# Actuator-Scratch_-_Cole.net
KiCad netlist of a schematic drawn in EAGLE
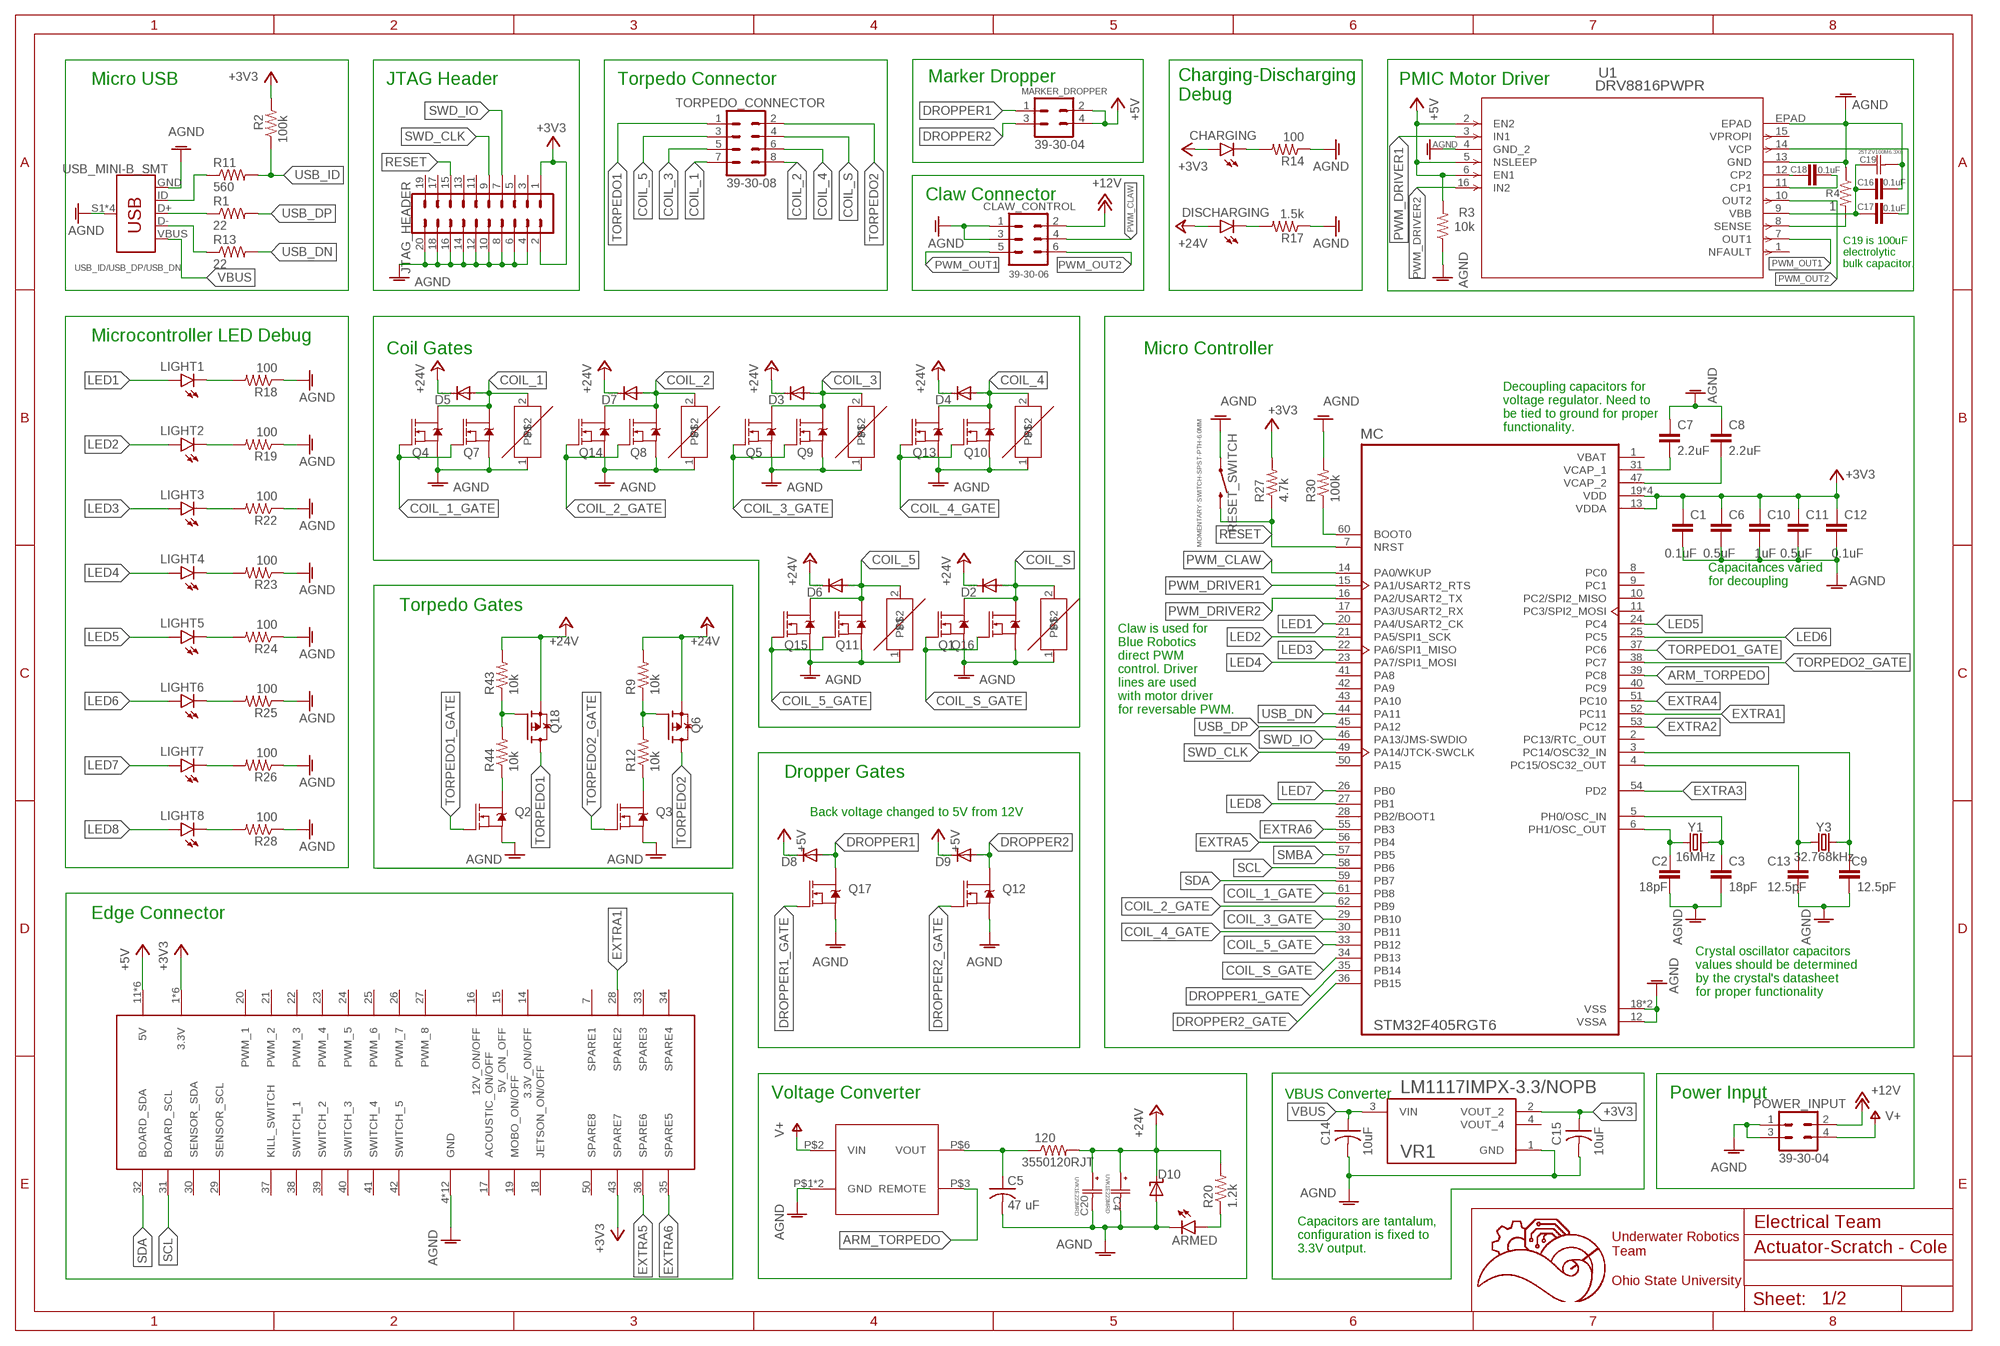
[diagram p0: schematic, sheet 1]
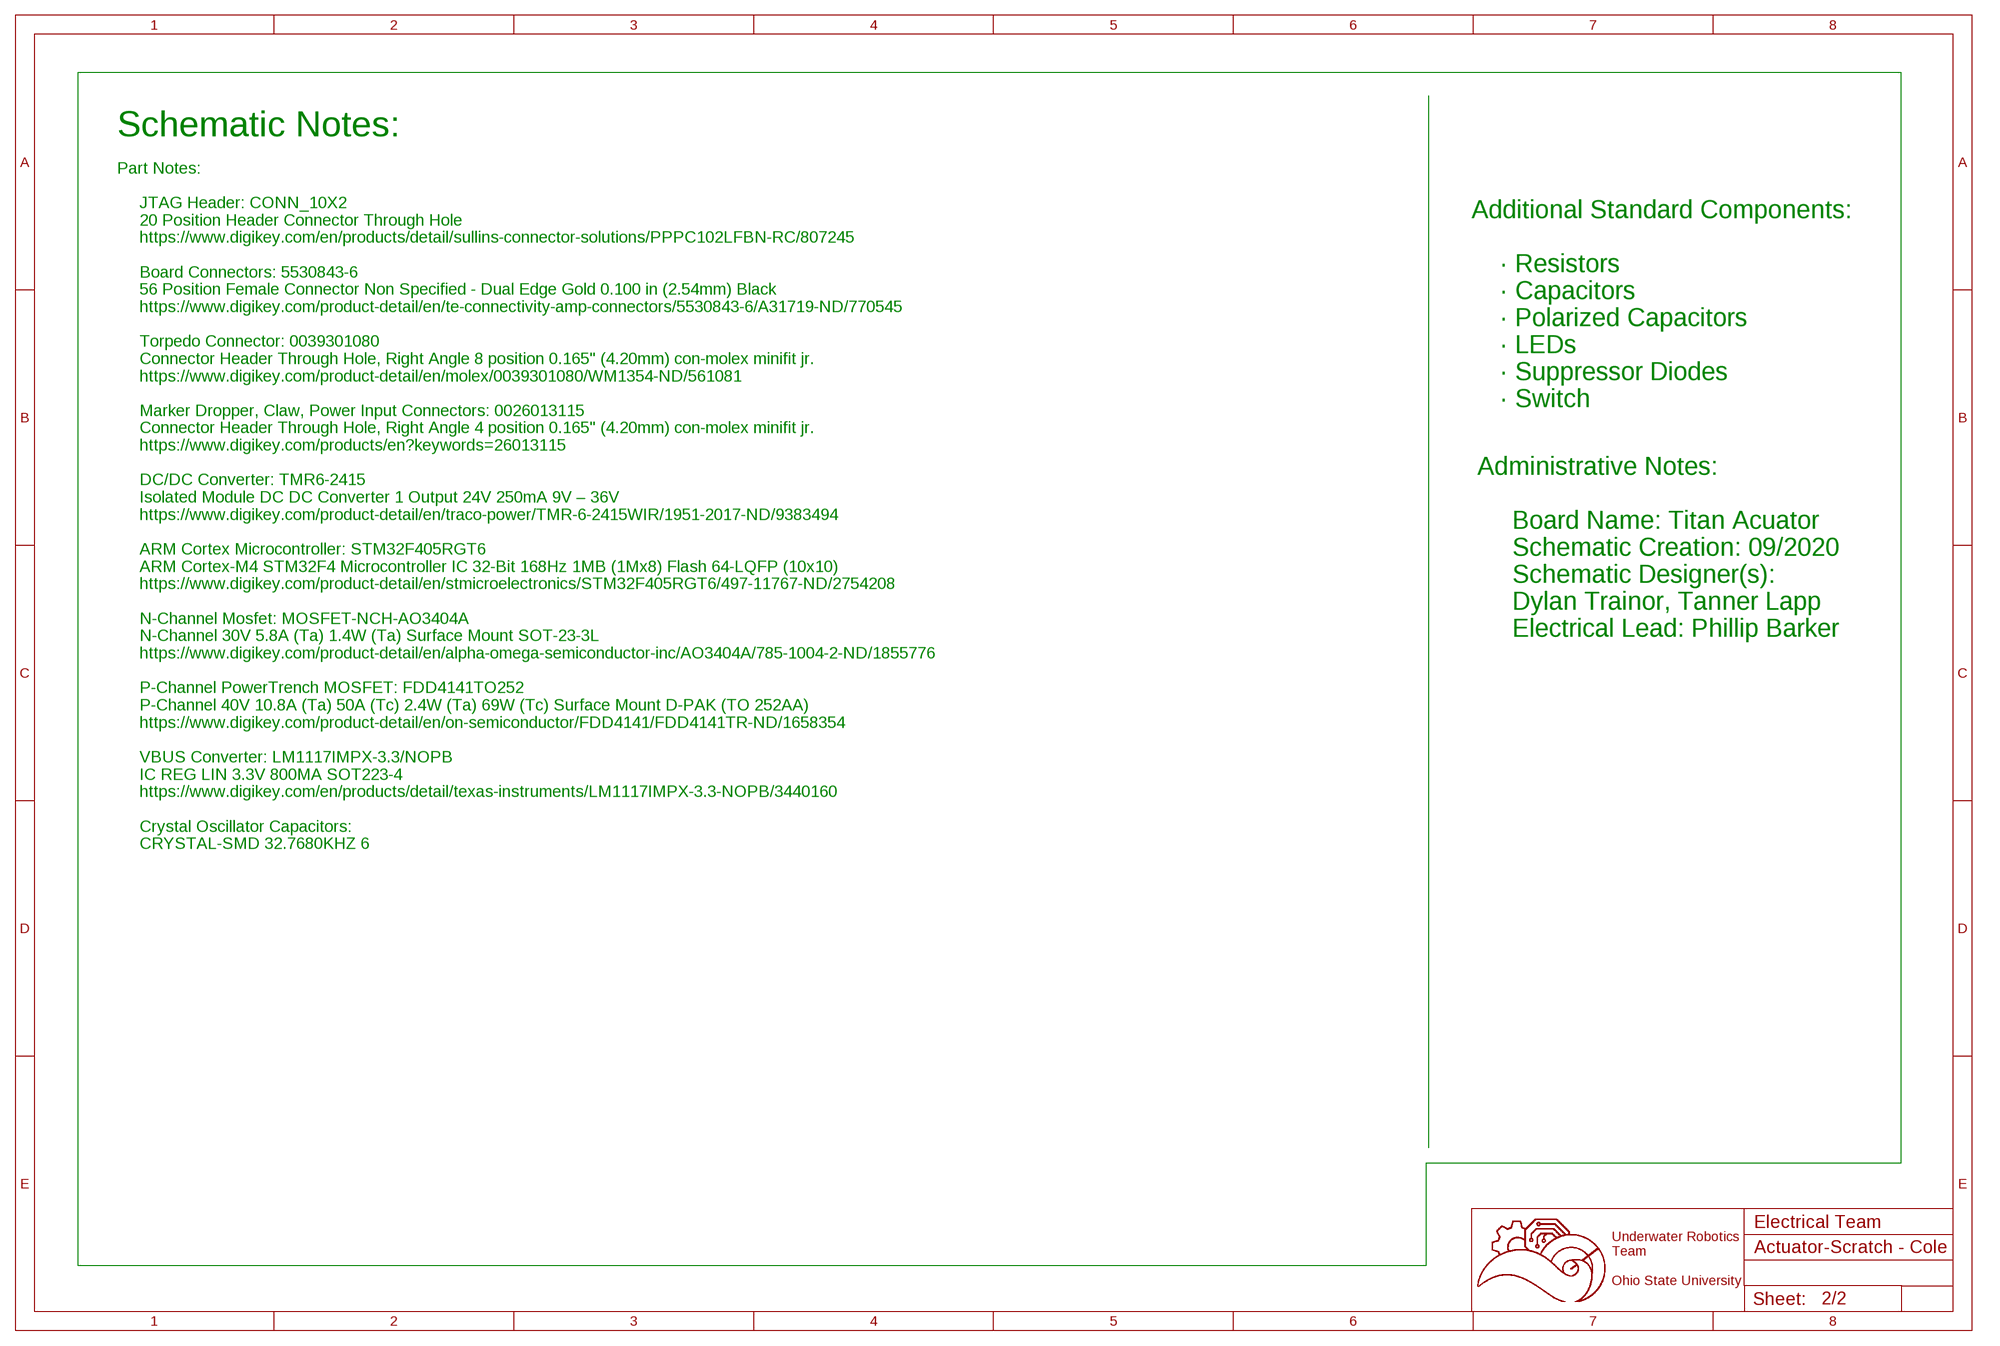
[diagram p1: schematic, sheet 2]

(export (version "E")
  (design (tool "Eeschema 10.0.6"))
  (components
    (comp (ref "120")
      (value "3550120RJT")
      (footprint "eagle-import:3550120RJT")
      (libsource (lib "eagle-import") (part "3550120RJT"))
    )
    (comp (ref "ARMED")
      (value "LEDCHIPLED_0603")
      (footprint "eagle-import:CHIPLED_0603")
      (libsource (lib "eagle-import") (part "LEDCHIPLED_0603"))
    )
    (comp (ref "C1")
      (value "0.1uF")
      (footprint "eagle-import:C0603")
      (libsource (lib "eagle-import") (part "C-EUC0603"))
    )
    (comp (ref "C2")
      (value "18pF")
      (footprint "eagle-import:C0603")
      (libsource (lib "eagle-import") (part "C-EUC0603"))
    )
    (comp (ref "C3")
      (value "18pF")
      (footprint "eagle-import:C0603")
      (libsource (lib "eagle-import") (part "C-EUC0603"))
    )
    (comp (ref "C4")
      (value "UVK1E223MRD")
      (footprint "eagle-import:CAP_UFW_25X50_NCH")
      (fields (field (name "COPYRIGHT") "Copyright (C) 2018 Accelerated Designs. All rights reserved"))
      (libsource (lib "eagle-import") (part "UVK1E223MRD"))
    )
    (comp (ref "C5")
      (value "47 uF")
      (footprint "eagle-import:C1206K")
      (libsource (lib "eagle-import") (part "resistor_348_C-USC1206K"))
    )
    (comp (ref "C6")
      (value "0.5uF")
      (footprint "eagle-import:C0603")
      (libsource (lib "eagle-import") (part "C-EUC0603"))
    )
    (comp (ref "C7")
      (value "2.2uF")
      (footprint "eagle-import:C0603")
      (libsource (lib "eagle-import") (part "C-EUC0603"))
    )
    (comp (ref "C8")
      (value "2.2uF")
      (footprint "eagle-import:C0603")
      (libsource (lib "eagle-import") (part "C-EUC0603"))
    )
    (comp (ref "C9")
      (value "12.5pF")
      (footprint "eagle-import:C0603")
      (libsource (lib "eagle-import") (part "C-EUC0603"))
    )
    (comp (ref "C10")
      (value "1uF")
      (footprint "eagle-import:C0603")
      (libsource (lib "eagle-import") (part "C-EUC0603"))
    )
    (comp (ref "C11")
      (value "0.5uF")
      (footprint "eagle-import:C0603")
      (libsource (lib "eagle-import") (part "C-EUC0603"))
    )
    (comp (ref "C12")
      (value "0.1uF")
      (footprint "eagle-import:C0603")
      (libsource (lib "eagle-import") (part "C-EUC0603"))
    )
    (comp (ref "C13")
      (value "12.5pF")
      (footprint "eagle-import:C0603")
      (libsource (lib "eagle-import") (part "C-EUC0603"))
    )
    (comp (ref "C14")
      (value "10uF")
      (footprint "eagle-import:C0603")
      (libsource (lib "eagle-import") (part "C-USC0603"))
    )
    (comp (ref "C15")
      (value "10uF")
      (footprint "eagle-import:C0603")
      (libsource (lib "eagle-import") (part "C-USC0603"))
    )
    (comp (ref "C16")
      (value "0.1uF")
      (footprint "eagle-import:C0603")
      (libsource (lib "eagle-import") (part "C-EUC0603"))
    )
    (comp (ref "C17")
      (value "0.1uF")
      (footprint "eagle-import:C0603")
      (libsource (lib "eagle-import") (part "C-EUC0603"))
    )
    (comp (ref "C18")
      (value "0.1uF")
      (footprint "eagle-import:C0603")
      (libsource (lib "eagle-import") (part "C-EUC0603"))
    )
    (comp (ref "C19")
      (value "25TZV100M6.3X8")
      (footprint "eagle-import:CAP_J-V_6P3X8_RUB")
      (fields (field (name "COPYRIGHT") "Copyright (C) 2018 Accelerated Designs. All rights reserved"))
      (libsource (lib "eagle-import") (part "25TZV100M6.3X8"))
    )
    (comp (ref "C20")
      (value "UVK1E223MRD")
      (footprint "eagle-import:CAP_UFW_25X50_NCH")
      (fields (field (name "COPYRIGHT") "Copyright (C) 2018 Accelerated Designs. All rights reserved"))
      (libsource (lib "eagle-import") (part "UVK1E223MRD"))
    )
    (comp (ref "CHARGING")
      (value "LEDCHIPLED_0603")
      (footprint "eagle-import:CHIPLED_0603")
      (libsource (lib "eagle-import") (part "LEDCHIPLED_0603"))
    )
    (comp (ref "CLAW_CONTROL")
      (value "39-30-06")
      (footprint "eagle-import:39-30-_06_")
      (libsource (lib "eagle-import") (part "39-30-?06?"))
    )
    (comp (ref "D2")
      (value "DIODE-SMB")
      (footprint "eagle-import:SMB")
      (libsource (lib "eagle-import") (part "DIODE-SMB"))
    )
    (comp (ref "D3")
      (value "DIODE-SMB")
      (footprint "eagle-import:SMB")
      (libsource (lib "eagle-import") (part "DIODE-SMB"))
    )
    (comp (ref "D4")
      (value "DIODE-SMB")
      (footprint "eagle-import:SMB")
      (libsource (lib "eagle-import") (part "DIODE-SMB"))
    )
    (comp (ref "D5")
      (value "DIODE-SMB")
      (footprint "eagle-import:SMB")
      (libsource (lib "eagle-import") (part "DIODE-SMB"))
    )
    (comp (ref "D6")
      (value "DIODE-SMB")
      (footprint "eagle-import:SMB")
      (libsource (lib "eagle-import") (part "DIODE-SMB"))
    )
    (comp (ref "D7")
      (value "DIODE-SMB")
      (footprint "eagle-import:SMB")
      (libsource (lib "eagle-import") (part "DIODE-SMB"))
    )
    (comp (ref "D8")
      (value "DIODE-SMB")
      (footprint "eagle-import:SMB")
      (libsource (lib "eagle-import") (part "DIODE-SMB"))
    )
    (comp (ref "D9")
      (value "DIODE-SMB")
      (footprint "eagle-import:SMB")
      (libsource (lib "eagle-import") (part "DIODE-SMB"))
    )
    (comp (ref "D10")
      (value "SUPPRESSOR-SMBJ")
      (footprint "eagle-import:SMBJ")
      (libsource (lib "eagle-import") (part "SUPPRESSOR-SMBJ"))
    )
    (comp (ref "DISCHARGING")
      (value "LEDCHIPLED_0603")
      (footprint "eagle-import:CHIPLED_0603")
      (libsource (lib "eagle-import") (part "LEDCHIPLED_0603"))
    )
    (comp (ref "JTAG_HEADER")
      (value "CONN_10X2")
      (footprint "eagle-import:2X10")
      (libsource (lib "eagle-import") (part "CONN_10X2"))
    )
    (comp (ref "LIGHT1")
      (value "LEDCHIPLED_0603")
      (footprint "eagle-import:CHIPLED_0603")
      (libsource (lib "eagle-import") (part "LEDCHIPLED_0603"))
    )
    (comp (ref "LIGHT2")
      (value "LEDCHIPLED_0603")
      (footprint "eagle-import:CHIPLED_0603")
      (libsource (lib "eagle-import") (part "LEDCHIPLED_0603"))
    )
    (comp (ref "LIGHT3")
      (value "LEDCHIPLED_0603")
      (footprint "eagle-import:CHIPLED_0603")
      (libsource (lib "eagle-import") (part "LEDCHIPLED_0603"))
    )
    (comp (ref "LIGHT4")
      (value "LEDCHIPLED_0603")
      (footprint "eagle-import:CHIPLED_0603")
      (libsource (lib "eagle-import") (part "LEDCHIPLED_0603"))
    )
    (comp (ref "LIGHT5")
      (value "LEDCHIPLED_0603")
      (footprint "eagle-import:CHIPLED_0603")
      (libsource (lib "eagle-import") (part "LEDCHIPLED_0603"))
    )
    (comp (ref "LIGHT6")
      (value "LEDCHIPLED_0603")
      (footprint "eagle-import:CHIPLED_0603")
      (libsource (lib "eagle-import") (part "LEDCHIPLED_0603"))
    )
    (comp (ref "LIGHT7")
      (value "LEDCHIPLED_0603")
      (footprint "eagle-import:CHIPLED_0603")
      (libsource (lib "eagle-import") (part "LEDCHIPLED_0603"))
    )
    (comp (ref "LIGHT8")
      (value "LEDCHIPLED_0603")
      (footprint "eagle-import:CHIPLED_0603")
      (libsource (lib "eagle-import") (part "LEDCHIPLED_0603"))
    )
    (comp (ref "MARKER_DROPPER")
      (value "39-30-04")
      (footprint "eagle-import:39-30-_04_")
      (libsource (lib "eagle-import") (part "39-30-?04?"))
    )
    (comp (ref "MC")
      (value "STM32F405RGT6")
      (footprint "eagle-import:QFP50P1200X1200X160-64N")
      (fields (field (name "MF") "STMicroelectronics"))
      (libsource (lib "eagle-import") (part "STM32F405RGT6"))
    )
    (comp (ref "POWER_INPUT")
      (value "39-30-04")
      (footprint "eagle-import:39-30-_04_")
      (libsource (lib "eagle-import") (part "39-30-?04?"))
    )
    (comp (ref "Q1")
      (value "MOSFET-NCH-AO3404A")
      (footprint "eagle-import:SOT23-3")
      (libsource (lib "eagle-import") (part "MOSFET-NCH-AO3404A"))
    )
    (comp (ref "Q2")
      (value "MOSFET-NCH-AO3404A")
      (footprint "eagle-import:SOT23-3")
      (libsource (lib "eagle-import") (part "MOSFET-NCH-AO3404A"))
    )
    (comp (ref "Q3")
      (value "MOSFET-NCH-AO3404A")
      (footprint "eagle-import:SOT23-3")
      (libsource (lib "eagle-import") (part "MOSFET-NCH-AO3404A"))
    )
    (comp (ref "Q4")
      (value "MOSFET-NCH-AO3404A")
      (footprint "eagle-import:SOT23-3")
      (libsource (lib "eagle-import") (part "MOSFET-NCH-AO3404A"))
    )
    (comp (ref "Q5")
      (value "MOSFET-NCH-AO3404A")
      (footprint "eagle-import:SOT23-3")
      (libsource (lib "eagle-import") (part "MOSFET-NCH-AO3404A"))
    )
    (comp (ref "Q6")
      (value "FDD4141TO252")
      (footprint "eagle-import:TO252")
      (libsource (lib "eagle-import") (part "FDD4141TO252"))
    )
    (comp (ref "Q7")
      (value "MOSFET-NCH-AO3404A")
      (footprint "eagle-import:SOT23-3")
      (libsource (lib "eagle-import") (part "MOSFET-NCH-AO3404A"))
    )
    (comp (ref "Q8")
      (value "MOSFET-NCH-AO3404A")
      (footprint "eagle-import:SOT23-3")
      (libsource (lib "eagle-import") (part "MOSFET-NCH-AO3404A"))
    )
    (comp (ref "Q9")
      (value "MOSFET-NCH-AO3404A")
      (footprint "eagle-import:SOT23-3")
      (libsource (lib "eagle-import") (part "MOSFET-NCH-AO3404A"))
    )
    (comp (ref "Q10")
      (value "MOSFET-NCH-AO3404A")
      (footprint "eagle-import:SOT23-3")
      (libsource (lib "eagle-import") (part "MOSFET-NCH-AO3404A"))
    )
    (comp (ref "Q11")
      (value "MOSFET-NCH-AO3404A")
      (footprint "eagle-import:SOT23-3")
      (libsource (lib "eagle-import") (part "MOSFET-NCH-AO3404A"))
    )
    (comp (ref "Q12")
      (value "MOSFET-NCH-AO3404A")
      (footprint "eagle-import:SOT23-3")
      (libsource (lib "eagle-import") (part "MOSFET-NCH-AO3404A"))
    )
    (comp (ref "Q13")
      (value "MOSFET-NCH-AO3404A")
      (footprint "eagle-import:SOT23-3")
      (libsource (lib "eagle-import") (part "MOSFET-NCH-AO3404A"))
    )
    (comp (ref "Q14")
      (value "MOSFET-NCH-AO3404A")
      (footprint "eagle-import:SOT23-3")
      (libsource (lib "eagle-import") (part "MOSFET-NCH-AO3404A"))
    )
    (comp (ref "Q15")
      (value "MOSFET-NCH-AO3404A")
      (footprint "eagle-import:SOT23-3")
      (libsource (lib "eagle-import") (part "MOSFET-NCH-AO3404A"))
    )
    (comp (ref "Q16")
      (value "MOSFET-NCH-AO3404A")
      (footprint "eagle-import:SOT23-3")
      (libsource (lib "eagle-import") (part "MOSFET-NCH-AO3404A"))
    )
    (comp (ref "Q17")
      (value "MOSFET-NCH-AO3404A")
      (footprint "eagle-import:SOT23-3")
      (libsource (lib "eagle-import") (part "MOSFET-NCH-AO3404A"))
    )
    (comp (ref "Q18")
      (value "FDD4141TO252")
      (footprint "eagle-import:TO252")
      (libsource (lib "eagle-import") (part "FDD4141TO252"))
    )
    (comp (ref "R1")
      (value "22")
      (footprint "eagle-import:R0603")
      (libsource (lib "eagle-import") (part "R-US_R0603"))
    )
    (comp (ref "R2")
      (value "100k")
      (footprint "eagle-import:R0603")
      (libsource (lib "eagle-import") (part "R-US_R0603"))
    )
    (comp (ref "R3")
      (value "10k")
      (footprint "eagle-import:R0603")
      (libsource (lib "eagle-import") (part "resistor_348_R-US_R0603"))
    )
    (comp (ref "R4")
      (value "1")
      (footprint "eagle-import:R0805")
      (libsource (lib "eagle-import") (part "resistor_348_R-US_R0805"))
    )
    (comp (ref "R9")
      (value "10k")
      (footprint "eagle-import:R0603")
      (libsource (lib "eagle-import") (part "resistor_348_R-US_R0603"))
    )
    (comp (ref "R11")
      (value "560")
      (footprint "eagle-import:R0603")
      (libsource (lib "eagle-import") (part "R-US_R0603"))
    )
    (comp (ref "R12")
      (value "10k")
      (footprint "eagle-import:R0603")
      (libsource (lib "eagle-import") (part "resistor_348_R-US_R0603"))
    )
    (comp (ref "R13")
      (value "22")
      (footprint "eagle-import:R0603")
      (libsource (lib "eagle-import") (part "R-US_R0603"))
    )
    (comp (ref "R14")
      (value "100")
      (footprint "eagle-import:R0805")
      (libsource (lib "eagle-import") (part "resistor_348_R-US_R0805"))
    )
    (comp (ref "R17")
      (value "1.5k")
      (footprint "eagle-import:R0805")
      (libsource (lib "eagle-import") (part "resistor_348_R-US_R0805"))
    )
    (comp (ref "R18")
      (value "100")
      (footprint "eagle-import:R0805")
      (libsource (lib "eagle-import") (part "resistor_348_R-US_R0805"))
    )
    (comp (ref "R19")
      (value "100")
      (footprint "eagle-import:R0805")
      (libsource (lib "eagle-import") (part "resistor_348_R-US_R0805"))
    )
    (comp (ref "R20")
      (value "1.2k")
      (footprint "eagle-import:R0805")
      (libsource (lib "eagle-import") (part "resistor_348_R-US_R0805"))
    )
    (comp (ref "R22")
      (value "100")
      (footprint "eagle-import:R0805")
      (libsource (lib "eagle-import") (part "resistor_348_R-US_R0805"))
    )
    (comp (ref "R23")
      (value "100")
      (footprint "eagle-import:R0805")
      (libsource (lib "eagle-import") (part "resistor_348_R-US_R0805"))
    )
    (comp (ref "R24")
      (value "100")
      (footprint "eagle-import:R0805")
      (libsource (lib "eagle-import") (part "resistor_348_R-US_R0805"))
    )
    (comp (ref "R25")
      (value "100")
      (footprint "eagle-import:R0805")
      (libsource (lib "eagle-import") (part "resistor_348_R-US_R0805"))
    )
    (comp (ref "R26")
      (value "100")
      (footprint "eagle-import:R0805")
      (libsource (lib "eagle-import") (part "resistor_348_R-US_R0805"))
    )
    (comp (ref "R27")
      (value "4.7k")
      (footprint "eagle-import:R0603")
      (libsource (lib "eagle-import") (part "R-US_R0603"))
    )
    (comp (ref "R28")
      (value "100")
      (footprint "eagle-import:R0805")
      (libsource (lib "eagle-import") (part "resistor_348_R-US_R0805"))
    )
    (comp (ref "R30")
      (value "100k")
      (footprint "eagle-import:R0603")
      (libsource (lib "eagle-import") (part "R-US_R0603"))
    )
    (comp (ref "R43")
      (value "10k")
      (footprint "eagle-import:R0603")
      (libsource (lib "eagle-import") (part "resistor_348_R-US_R0603"))
    )
    (comp (ref "R44")
      (value "10k")
      (footprint "eagle-import:R0603")
      (libsource (lib "eagle-import") (part "resistor_348_R-US_R0603"))
    )
    (comp (ref "RESET_SWITCH")
      (value "MOMENTARY-SWITCH-SPST-PTH-6.0MM")
      (footprint "eagle-import:TACTILE_SWITCH_PTH_6.0MM")
      (libsource (lib "eagle-import") (part "MOMENTARY-SWITCH-SPST-PTH-6.0MM"))
    )
    (comp (ref "TORPEDO_CONNECTOR")
      (value "39-30-08")
      (footprint "eagle-import:39-30-_08_")
      (libsource (lib "eagle-import") (part "39-30-?08?"))
    )
    (comp (ref "U$1")
      (value "5530843-EDGE")
      (footprint "eagle-import:5530843-6-BOARDFINGERS")
      (libsource (lib "eagle-import") (part "5530843-EDGE"))
    )
    (comp (ref "U$2")
      (value "ERZ-VF2M270ERZ-VF2M270")
      (footprint "eagle-import:RESM8060X320N")
      (libsource (lib "eagle-import") (part "ERZ-VF2M270ERZ-VF2M270"))
    )
    (comp (ref "U$3")
      (value "ERZ-VF2M270ERZ-VF2M270")
      (footprint "eagle-import:RESM8060X320N")
      (libsource (lib "eagle-import") (part "ERZ-VF2M270ERZ-VF2M270"))
    )
    (comp (ref "U$4")
      (value "ERZ-VF2M270ERZ-VF2M270")
      (footprint "eagle-import:RESM8060X320N")
      (libsource (lib "eagle-import") (part "ERZ-VF2M270ERZ-VF2M270"))
    )
    (comp (ref "U$5")
      (value "ERZ-VF2M270ERZ-VF2M270")
      (footprint "eagle-import:RESM8060X320N")
      (libsource (lib "eagle-import") (part "ERZ-VF2M270ERZ-VF2M270"))
    )
    (comp (ref "U$6")
      (value "TMR6-2415")
      (footprint "eagle-import:TMR6-2415")
      (libsource (lib "eagle-import") (part "TMR6-2415"))
    )
    (comp (ref "U$7")
      (value "ERZ-VF2M270ERZ-VF2M270")
      (footprint "eagle-import:RESM8060X320N")
      (libsource (lib "eagle-import") (part "ERZ-VF2M270ERZ-VF2M270"))
    )
    (comp (ref "U$8")
      (value "ERZ-VF2M270ERZ-VF2M270")
      (footprint "eagle-import:RESM8060X320N")
      (libsource (lib "eagle-import") (part "ERZ-VF2M270ERZ-VF2M270"))
    )
    (comp (ref "U1")
      (value "DRV8816PWPR")
      (footprint "eagle-import:PWP_16")
      (libsource (lib "eagle-import") (part "DRV8816PWPR"))
    )
    (comp (ref "USB_ID/USB_DP/USB_DN")
      (value "USB_MINI-B_SMT")
      (footprint "eagle-import:USB-MINIB")
      (libsource (lib "eagle-import") (part "USB_MINI-B_SMT"))
    )
    (comp (ref "VR1")
      (value "LM1117IMPX-3.3/NOPB")
      (footprint "eagle-import:VREG_LM1117IMPX-3.3_NOPB")
      (fields (field (name "MF") "Texas Instruments"))
      (libsource (lib "eagle-import") (part "LM1117IMPX-3.3/NOPB"))
    )
    (comp (ref "Y1")
      (value "16MHz")
      (footprint "eagle-import:HC49US")
      (libsource (lib "eagle-import") (part "CRYSTAL-16MHZPTH-HC49US"))
    )
    (comp (ref "Y3")
      (value "32.768kHz")
      (footprint "eagle-import:CRYSTAL-SMD-3.2X1.5MM")
      (libsource (lib "eagle-import") (part "CRYSTAL-32.768KHZSMD-3.2X1.5"))
    )
  )
  (nets
    (net (code "1") (name "+3V3") (class "Default")
      (node (ref "C1") (pin "1") (pinfunction "1_1") (pintype "passive"))
      (node (ref "C10") (pin "1") (pinfunction "1_1") (pintype "passive"))
      (node (ref "C11") (pin "1") (pinfunction "1_1") (pintype "passive"))
      (node (ref "C12") (pin "1") (pinfunction "1_1") (pintype "passive"))
      (node (ref "C15") (pin "1") (pinfunction "1_1") (pintype "passive"))
      (node (ref "C6") (pin "1") (pinfunction "1_1") (pintype "passive"))
      (node (ref "CHARGING") (pin "A") (pinfunction "A_A") (pintype "passive"))
      (node (ref "JTAG_HEADER") (pin "1") (pinfunction "1_1") (pintype "passive"))
      (node (ref "JTAG_HEADER") (pin "2") (pinfunction "2_2") (pintype "passive"))
      (node (ref "MC") (pin "13") (pinfunction "VDDA_13") (pintype "power_in"))
      (node (ref "MC") (pin "19") (pinfunction "VDD_19") (pintype "power_in"))
      (node (ref "MC") (pin "32") (pinfunction "VDD_32") (pintype "power_in"))
      (node (ref "MC") (pin "48") (pinfunction "VDD_48") (pintype "power_in"))
      (node (ref "MC") (pin "64") (pinfunction "VDD_64") (pintype "power_in"))
      (node (ref "R2") (pin "2") (pinfunction "2_2") (pintype "passive"))
      (node (ref "R27") (pin "2") (pinfunction "2_2") (pintype "passive"))
      (node (ref "U$1") (pin "1") (pinfunction "3.3V_1") (pintype "bidirectional"))
      (node (ref "U$1") (pin "2") (pinfunction "3.3V_2") (pintype "bidirectional"))
      (node (ref "U$1") (pin "3") (pinfunction "3.3V_3") (pintype "bidirectional"))
      (node (ref "U$1") (pin "43") (pinfunction "SPARE7_43") (pintype "bidirectional"))
      (node (ref "U$1") (pin "54") (pinfunction "3.3V_54") (pintype "bidirectional"))
      (node (ref "U$1") (pin "55") (pinfunction "3.3V_55") (pintype "bidirectional"))
      (node (ref "U$1") (pin "56") (pinfunction "3.3V_56") (pintype "bidirectional"))
      (node (ref "VR1") (pin "2") (pinfunction "VOUT_2_2") (pintype "output"))
    )
    (net (code "2") (name "+5V") (class "Default")
      (node (ref "D8") (pin "C") (pinfunction "C_C") (pintype "passive"))
      (node (ref "D9") (pin "C") (pinfunction "C_C") (pintype "passive"))
      (node (ref "MARKER_DROPPER") (pin "2") (pinfunction "2_2") (pintype "passive"))
      (node (ref "MARKER_DROPPER") (pin "4") (pinfunction "4_4") (pintype "passive"))
      (node (ref "R3") (pin "2") (pinfunction "2_2") (pintype "passive"))
      (node (ref "U$1") (pin "11") (pinfunction "5V_11") (pintype "bidirectional"))
      (node (ref "U$1") (pin "12") (pinfunction "5V_12") (pintype "bidirectional"))
      (node (ref "U$1") (pin "13") (pinfunction "5V_13") (pintype "bidirectional"))
      (node (ref "U$1") (pin "44") (pinfunction "5V_44") (pintype "bidirectional"))
      (node (ref "U$1") (pin "45") (pinfunction "5V_45") (pintype "bidirectional"))
      (node (ref "U$1") (pin "46") (pinfunction "5V_46") (pintype "bidirectional"))
      (node (ref "U1") (pin "2") (pinfunction "EN2_2") (pintype "input"))
      (node (ref "U1") (pin "5") (pinfunction "NSLEEP_5") (pintype "input"))
      (node (ref "U1") (pin "6") (pinfunction "EN1_6") (pintype "input"))
    )
    (net (code "3") (name "+12V") (class "Default")
      (node (ref "CLAW_CONTROL") (pin "2") (pinfunction "2_2") (pintype "passive"))
      (node (ref "POWER_INPUT") (pin "2") (pinfunction "2_2") (pintype "passive"))
    )
    (net (code "4") (name "+24V") (class "Default")
      (node (ref "120") (pin "P$2") (pinfunction "2_P$2") (pintype "passive"))
      (node (ref "C20") (pin "1") (pinfunction "1_1") (pintype "passive"))
      (node (ref "C4") (pin "1") (pinfunction "1_1") (pintype "passive"))
      (node (ref "D10") (pin "C") (pinfunction "C_C") (pintype "passive"))
      (node (ref "D2") (pin "C") (pinfunction "C_C") (pintype "passive"))
      (node (ref "D3") (pin "C") (pinfunction "C_C") (pintype "passive"))
      (node (ref "D4") (pin "C") (pinfunction "C_C") (pintype "passive"))
      (node (ref "D5") (pin "C") (pinfunction "C_C") (pintype "passive"))
      (node (ref "D6") (pin "C") (pinfunction "C_C") (pintype "passive"))
      (node (ref "D7") (pin "C") (pinfunction "C_C") (pintype "passive"))
      (node (ref "DISCHARGING") (pin "A") (pinfunction "A_A") (pintype "passive"))
      (node (ref "Q18") (pin "2") (pinfunction "S_2") (pintype "passive"))
      (node (ref "Q6") (pin "2") (pinfunction "S_2") (pintype "passive"))
      (node (ref "R20") (pin "2") (pinfunction "2_2") (pintype "passive"))
      (node (ref "R43") (pin "2") (pinfunction "2_2") (pintype "passive"))
      (node (ref "R9") (pin "2") (pinfunction "2_2") (pintype "passive"))
    )
    (net (code "5") (name "AGND") (class "Default")
      (node (ref "ARMED") (pin "C") (pinfunction "C_C") (pintype "passive"))
      (node (ref "C1") (pin "2") (pinfunction "2_2") (pintype "passive"))
      (node (ref "C10") (pin "2") (pinfunction "2_2") (pintype "passive"))
      (node (ref "C11") (pin "2") (pinfunction "2_2") (pintype "passive"))
      (node (ref "C12") (pin "2") (pinfunction "2_2") (pintype "passive"))
      (node (ref "C13") (pin "2") (pinfunction "2_2") (pintype "passive"))
      (node (ref "C14") (pin "2") (pinfunction "2_2") (pintype "passive"))
      (node (ref "C15") (pin "2") (pinfunction "2_2") (pintype "passive"))
      (node (ref "C16") (pin "2") (pinfunction "2_2") (pintype "passive"))
      (node (ref "C19") (pin "2") (pinfunction "2_2") (pintype "passive"))
      (node (ref "C2") (pin "2") (pinfunction "2_2") (pintype "passive"))
      (node (ref "C20") (pin "2") (pinfunction "2_2") (pintype "passive"))
      (node (ref "C3") (pin "2") (pinfunction "2_2") (pintype "passive"))
      (node (ref "C4") (pin "2") (pinfunction "2_2") (pintype "passive"))
      (node (ref "C5") (pin "2") (pinfunction "2_2") (pintype "passive"))
      (node (ref "C6") (pin "2") (pinfunction "2_2") (pintype "passive"))
      (node (ref "C7") (pin "1") (pinfunction "1_1") (pintype "passive"))
      (node (ref "C8") (pin "1") (pinfunction "1_1") (pintype "passive"))
      (node (ref "C9") (pin "2") (pinfunction "2_2") (pintype "passive"))
      (node (ref "CLAW_CONTROL") (pin "1") (pinfunction "1_1") (pintype "passive"))
      (node (ref "CLAW_CONTROL") (pin "3") (pinfunction "3_3") (pintype "passive"))
      (node (ref "D10") (pin "A") (pinfunction "A_A") (pintype "passive"))
      (node (ref "JTAG_HEADER") (pin "10") (pinfunction "10_10") (pintype "passive"))
      (node (ref "JTAG_HEADER") (pin "12") (pinfunction "12_12") (pintype "passive"))
      (node (ref "JTAG_HEADER") (pin "14") (pinfunction "14_14") (pintype "passive"))
      (node (ref "JTAG_HEADER") (pin "16") (pinfunction "16_16") (pintype "passive"))
      (node (ref "JTAG_HEADER") (pin "18") (pinfunction "18_18") (pintype "passive"))
      (node (ref "JTAG_HEADER") (pin "20") (pinfunction "20_20") (pintype "passive"))
      (node (ref "JTAG_HEADER") (pin "4") (pinfunction "4_4") (pintype "passive"))
      (node (ref "JTAG_HEADER") (pin "6") (pinfunction "6_6") (pintype "passive"))
      (node (ref "JTAG_HEADER") (pin "8") (pinfunction "8_8") (pintype "passive"))
      (node (ref "MC") (pin "12") (pinfunction "VSSA_12") (pintype "power_in"))
      (node (ref "MC") (pin "18") (pinfunction "VSS_18") (pintype "power_in"))
      (node (ref "MC") (pin "63") (pinfunction "VSS_63") (pintype "power_in"))
      (node (ref "POWER_INPUT") (pin "1") (pinfunction "1_1") (pintype "passive"))
      (node (ref "POWER_INPUT") (pin "3") (pinfunction "3_3") (pintype "passive"))
      (node (ref "Q1") (pin "2") (pinfunction "S_2") (pintype "bidirectional"))
      (node (ref "Q10") (pin "2") (pinfunction "S_2") (pintype "bidirectional"))
      (node (ref "Q11") (pin "2") (pinfunction "S_2") (pintype "bidirectional"))
      (node (ref "Q12") (pin "2") (pinfunction "S_2") (pintype "bidirectional"))
      (node (ref "Q13") (pin "2") (pinfunction "S_2") (pintype "bidirectional"))
      (node (ref "Q14") (pin "2") (pinfunction "S_2") (pintype "bidirectional"))
      (node (ref "Q15") (pin "2") (pinfunction "S_2") (pintype "bidirectional"))
      (node (ref "Q16") (pin "2") (pinfunction "S_2") (pintype "bidirectional"))
      (node (ref "Q17") (pin "2") (pinfunction "S_2") (pintype "bidirectional"))
      (node (ref "Q2") (pin "2") (pinfunction "S_2") (pintype "bidirectional"))
      (node (ref "Q3") (pin "2") (pinfunction "S_2") (pintype "bidirectional"))
      (node (ref "Q4") (pin "2") (pinfunction "S_2") (pintype "bidirectional"))
      (node (ref "Q5") (pin "2") (pinfunction "S_2") (pintype "bidirectional"))
      (node (ref "Q7") (pin "2") (pinfunction "S_2") (pintype "bidirectional"))
      (node (ref "Q8") (pin "2") (pinfunction "S_2") (pintype "bidirectional"))
      (node (ref "Q9") (pin "2") (pinfunction "S_2") (pintype "bidirectional"))
      (node (ref "R14") (pin "1") (pinfunction "1_1") (pintype "passive"))
      (node (ref "R17") (pin "1") (pinfunction "1_1") (pintype "passive"))
      (node (ref "R18") (pin "1") (pinfunction "1_1") (pintype "passive"))
      (node (ref "R19") (pin "1") (pinfunction "1_1") (pintype "passive"))
      (node (ref "R22") (pin "1") (pinfunction "1_1") (pintype "passive"))
      (node (ref "R23") (pin "1") (pinfunction "1_1") (pintype "passive"))
      (node (ref "R24") (pin "1") (pinfunction "1_1") (pintype "passive"))
      (node (ref "R25") (pin "1") (pinfunction "1_1") (pintype "passive"))
      (node (ref "R26") (pin "1") (pinfunction "1_1") (pintype "passive"))
      (node (ref "R28") (pin "1") (pinfunction "1_1") (pintype "passive"))
      (node (ref "R3") (pin "1") (pinfunction "1_1") (pintype "passive"))
      (node (ref "R30") (pin "2") (pinfunction "2_2") (pintype "passive"))
      (node (ref "R4") (pin "1") (pinfunction "1_1") (pintype "passive"))
      (node (ref "RESET_SWITCH") (pin "1") (pinfunction "1_1") (pintype "passive"))
      (node (ref "U$1") (pin "10") (pinfunction "GND_10") (pintype "bidirectional"))
      (node (ref "U$1") (pin "4") (pinfunction "GND_4") (pintype "bidirectional"))
      (node (ref "U$1") (pin "47") (pinfunction "GND_47") (pintype "bidirectional"))
      (node (ref "U$1") (pin "48") (pinfunction "GND_48") (pintype "bidirectional"))
      (node (ref "U$1") (pin "49") (pinfunction "GND_49") (pintype "bidirectional"))
      (node (ref "U$1") (pin "5") (pinfunction "GND_5") (pintype "bidirectional"))
      (node (ref "U$1") (pin "51") (pinfunction "GND_51") (pintype "bidirectional"))
      (node (ref "U$1") (pin "52") (pinfunction "GND_52") (pintype "bidirectional"))
      (node (ref "U$1") (pin "53") (pinfunction "GND_53") (pintype "bidirectional"))
      (node (ref "U$1") (pin "6") (pinfunction "GND_6") (pintype "bidirectional"))
      (node (ref "U$1") (pin "8") (pinfunction "GND_8") (pintype "bidirectional"))
      (node (ref "U$1") (pin "9") (pinfunction "GND_9") (pintype "bidirectional"))
      (node (ref "U$2") (pin "1") (pinfunction "P$1_1") (pintype "bidirectional"))
      (node (ref "U$3") (pin "1") (pinfunction "P$1_1") (pintype "bidirectional"))
      (node (ref "U$4") (pin "1") (pinfunction "P$1_1") (pintype "bidirectional"))
      (node (ref "U$5") (pin "1") (pinfunction "P$1_1") (pintype "bidirectional"))
      (node (ref "U$6") (pin "P$1") (pinfunction "GND_P$1") (pintype "bidirectional"))
      (node (ref "U$6") (pin "P$7") (pinfunction "GND_P$7") (pintype "bidirectional"))
      (node (ref "U$7") (pin "1") (pinfunction "P$1_1") (pintype "bidirectional"))
      (node (ref "U$8") (pin "1") (pinfunction "P$1_1") (pintype "bidirectional"))
      (node (ref "U1") (pin "13") (pinfunction "GND_13") (pintype "power_in"))
      (node (ref "U1") (pin "4") (pinfunction "GND_2_4") (pintype "power_in"))
      (node (ref "U1") (pin "EPAD") (pinfunction "EPAD_EPAD") (pintype "passive"))
      (node (ref "USB_ID/USB_DP/USB_DN") (pin "GND") (pinfunction "GND_GND") (pintype "power_in"))
      (node (ref "USB_ID/USB_DP/USB_DN") (pin "S1") (pinfunction "SHIELD_S1") (pintype "bidirectional"))
      (node (ref "USB_ID/USB_DP/USB_DN") (pin "S2") (pinfunction "SHIELD_S2") (pintype "bidirectional"))
      (node (ref "USB_ID/USB_DP/USB_DN") (pin "S3") (pinfunction "SHIELD_S3") (pintype "bidirectional"))
      (node (ref "USB_ID/USB_DP/USB_DN") (pin "S4") (pinfunction "SHIELD_S4") (pintype "bidirectional"))
      (node (ref "VR1") (pin "1") (pinfunction "GND_1") (pintype "power_in"))
    )
    (net (code "6") (name "ARM_TORPEDO") (class "Default")
      (node (ref "MC") (pin "39") (pinfunction "PC8_39") (pintype "bidirectional"))
      (node (ref "U$6") (pin "P$3") (pinfunction "REMOTE_P$3") (pintype "bidirectional"))
    )
    (net (code "7") (name "COIL_1") (class "Default")
      (node (ref "D5") (pin "A") (pinfunction "A_A") (pintype "passive"))
      (node (ref "Q4") (pin "3") (pinfunction "D_3") (pintype "bidirectional"))
      (node (ref "Q7") (pin "3") (pinfunction "D_3") (pintype "bidirectional"))
      (node (ref "TORPEDO_CONNECTOR") (pin "7") (pinfunction "7_7") (pintype "passive"))
      (node (ref "U$8") (pin "2") (pinfunction "P$2_2") (pintype "bidirectional"))
    )
    (net (code "8") (name "COIL_1_GATE") (class "Default")
      (node (ref "MC") (pin "61") (pinfunction "PB8_61") (pintype "bidirectional"))
      (node (ref "Q4") (pin "1") (pinfunction "G_1") (pintype "bidirectional"))
      (node (ref "Q7") (pin "1") (pinfunction "G_1") (pintype "bidirectional"))
    )
    (net (code "9") (name "COIL_2") (class "Default")
      (node (ref "D7") (pin "A") (pinfunction "A_A") (pintype "passive"))
      (node (ref "Q14") (pin "3") (pinfunction "D_3") (pintype "bidirectional"))
      (node (ref "Q8") (pin "3") (pinfunction "D_3") (pintype "bidirectional"))
      (node (ref "TORPEDO_CONNECTOR") (pin "8") (pinfunction "8_8") (pintype "passive"))
      (node (ref "U$7") (pin "2") (pinfunction "P$2_2") (pintype "bidirectional"))
    )
    (net (code "10") (name "COIL_2_GATE") (class "Default")
      (node (ref "MC") (pin "62") (pinfunction "PB9_62") (pintype "bidirectional"))
      (node (ref "Q14") (pin "1") (pinfunction "G_1") (pintype "bidirectional"))
      (node (ref "Q8") (pin "1") (pinfunction "G_1") (pintype "bidirectional"))
    )
    (net (code "11") (name "COIL_3") (class "Default")
      (node (ref "D3") (pin "A") (pinfunction "A_A") (pintype "passive"))
      (node (ref "Q5") (pin "3") (pinfunction "D_3") (pintype "bidirectional"))
      (node (ref "Q9") (pin "3") (pinfunction "D_3") (pintype "bidirectional"))
      (node (ref "TORPEDO_CONNECTOR") (pin "5") (pinfunction "5_5") (pintype "passive"))
      (node (ref "U$5") (pin "2") (pinfunction "P$2_2") (pintype "bidirectional"))
    )
    (net (code "12") (name "COIL_3_GATE") (class "Default")
      (node (ref "MC") (pin "29") (pinfunction "PB10_29") (pintype "bidirectional"))
      (node (ref "Q5") (pin "1") (pinfunction "G_1") (pintype "bidirectional"))
      (node (ref "Q9") (pin "1") (pinfunction "G_1") (pintype "bidirectional"))
    )
    (net (code "13") (name "COIL_4") (class "Default")
      (node (ref "D4") (pin "A") (pinfunction "A_A") (pintype "passive"))
      (node (ref "Q10") (pin "3") (pinfunction "D_3") (pintype "bidirectional"))
      (node (ref "Q13") (pin "3") (pinfunction "D_3") (pintype "bidirectional"))
      (node (ref "TORPEDO_CONNECTOR") (pin "6") (pinfunction "6_6") (pintype "passive"))
      (node (ref "U$4") (pin "2") (pinfunction "P$2_2") (pintype "bidirectional"))
    )
    (net (code "14") (name "COIL_4_GATE") (class "Default")
      (node (ref "MC") (pin "30") (pinfunction "PB11_30") (pintype "bidirectional"))
      (node (ref "Q10") (pin "1") (pinfunction "G_1") (pintype "bidirectional"))
      (node (ref "Q13") (pin "1") (pinfunction "G_1") (pintype "bidirectional"))
    )
    (net (code "15") (name "COIL_5") (class "Default")
      (node (ref "D6") (pin "A") (pinfunction "A_A") (pintype "passive"))
      (node (ref "Q11") (pin "3") (pinfunction "D_3") (pintype "bidirectional"))
      (node (ref "Q15") (pin "3") (pinfunction "D_3") (pintype "bidirectional"))
      (node (ref "TORPEDO_CONNECTOR") (pin "3") (pinfunction "3_3") (pintype "passive"))
      (node (ref "U$3") (pin "2") (pinfunction "P$2_2") (pintype "bidirectional"))
    )
    (net (code "16") (name "COIL_5_GATE") (class "Default")
      (node (ref "MC") (pin "33") (pinfunction "PB12_33") (pintype "bidirectional"))
      (node (ref "Q11") (pin "1") (pinfunction "G_1") (pintype "bidirectional"))
      (node (ref "Q15") (pin "1") (pinfunction "G_1") (pintype "bidirectional"))
    )
    (net (code "17") (name "COIL_S") (class "Default")
      (node (ref "D2") (pin "A") (pinfunction "A_A") (pintype "passive"))
      (node (ref "Q1") (pin "3") (pinfunction "D_3") (pintype "bidirectional"))
      (node (ref "Q16") (pin "3") (pinfunction "D_3") (pintype "bidirectional"))
      (node (ref "TORPEDO_CONNECTOR") (pin "4") (pinfunction "4_4") (pintype "passive"))
      (node (ref "U$2") (pin "2") (pinfunction "P$2_2") (pintype "bidirectional"))
    )
    (net (code "18") (name "COIL_S_GATE") (class "Default")
      (node (ref "MC") (pin "34") (pinfunction "PB13_34") (pintype "bidirectional"))
      (node (ref "Q1") (pin "1") (pinfunction "G_1") (pintype "bidirectional"))
      (node (ref "Q16") (pin "1") (pinfunction "G_1") (pintype "bidirectional"))
    )
    (net (code "19") (name "DROPPER1") (class "Default")
      (node (ref "D8") (pin "A") (pinfunction "A_A") (pintype "passive"))
      (node (ref "MARKER_DROPPER") (pin "1") (pinfunction "1_1") (pintype "passive"))
      (node (ref "Q17") (pin "3") (pinfunction "D_3") (pintype "bidirectional"))
    )
    (net (code "20") (name "DROPPER1_GATE") (class "Default")
      (node (ref "MC") (pin "35") (pinfunction "PB14_35") (pintype "bidirectional"))
      (node (ref "Q17") (pin "1") (pinfunction "G_1") (pintype "bidirectional"))
    )
    (net (code "21") (name "DROPPER2") (class "Default")
      (node (ref "D9") (pin "A") (pinfunction "A_A") (pintype "passive"))
      (node (ref "MARKER_DROPPER") (pin "3") (pinfunction "3_3") (pintype "passive"))
      (node (ref "Q12") (pin "3") (pinfunction "D_3") (pintype "bidirectional"))
    )
    (net (code "22") (name "DROPPER2_GATE") (class "Default")
      (node (ref "MC") (pin "36") (pinfunction "PB15_36") (pintype "bidirectional"))
      (node (ref "Q12") (pin "1") (pinfunction "G_1") (pintype "bidirectional"))
    )
    (net (code "23") (name "EXTRA1") (class "Default")
      (node (ref "MC") (pin "52") (pinfunction "PC11_52") (pintype "bidirectional"))
      (node (ref "U$1") (pin "28") (pinfunction "SPARE2_28") (pintype "bidirectional"))
    )
    (net (code "24") (name "EXTRA2") (class "Default")
      (node (ref "MC") (pin "53") (pinfunction "PC12_53") (pintype "bidirectional"))
    )
    (net (code "25") (name "EXTRA3") (class "Default")
      (node (ref "MC") (pin "54") (pinfunction "PD2_54") (pintype "bidirectional"))
    )
    (net (code "26") (name "EXTRA4") (class "Default")
      (node (ref "MC") (pin "51") (pinfunction "PC10_51") (pintype "bidirectional"))
    )
    (net (code "27") (name "EXTRA5") (class "Default")
      (node (ref "MC") (pin "56") (pinfunction "PB4_56") (pintype "bidirectional"))
      (node (ref "U$1") (pin "36") (pinfunction "SPARE6_36") (pintype "bidirectional"))
    )
    (net (code "28") (name "EXTRA6") (class "Default")
      (node (ref "MC") (pin "55") (pinfunction "PB3_55") (pintype "bidirectional"))
      (node (ref "U$1") (pin "35") (pinfunction "SPARE5_35") (pintype "bidirectional"))
    )
    (net (code "29") (name "LED1") (class "Default")
      (node (ref "LIGHT1") (pin "A") (pinfunction "A_A") (pintype "passive"))
      (node (ref "MC") (pin "20") (pinfunction "PA4/USART2_CK_20") (pintype "bidirectional"))
    )
    (net (code "30") (name "LED2") (class "Default")
      (node (ref "LIGHT2") (pin "A") (pinfunction "A_A") (pintype "passive"))
      (node (ref "MC") (pin "21") (pinfunction "PA5/SPI1_SCK_21") (pintype "bidirectional"))
    )
    (net (code "31") (name "LED3") (class "Default")
      (node (ref "LIGHT3") (pin "A") (pinfunction "A_A") (pintype "passive"))
      (node (ref "MC") (pin "22") (pinfunction "PA6/SPI1_MISO_22") (pintype "bidirectional"))
    )
    (net (code "32") (name "LED4") (class "Default")
      (node (ref "LIGHT4") (pin "A") (pinfunction "A_A") (pintype "passive"))
      (node (ref "MC") (pin "23") (pinfunction "PA7/SPI1_MOSI_23") (pintype "bidirectional"))
    )
    (net (code "33") (name "LED5") (class "Default")
      (node (ref "LIGHT5") (pin "A") (pinfunction "A_A") (pintype "passive"))
      (node (ref "MC") (pin "24") (pinfunction "PC4_24") (pintype "bidirectional"))
    )
    (net (code "34") (name "LED6") (class "Default")
      (node (ref "LIGHT6") (pin "A") (pinfunction "A_A") (pintype "passive"))
      (node (ref "MC") (pin "25") (pinfunction "PC5_25") (pintype "bidirectional"))
    )
    (net (code "35") (name "LED7") (class "Default")
      (node (ref "LIGHT7") (pin "A") (pinfunction "A_A") (pintype "passive"))
      (node (ref "MC") (pin "26") (pinfunction "PB0_26") (pintype "bidirectional"))
    )
    (net (code "36") (name "LED8") (class "Default")
      (node (ref "LIGHT8") (pin "A") (pinfunction "A_A") (pintype "passive"))
      (node (ref "MC") (pin "27") (pinfunction "PB1_27") (pintype "bidirectional"))
    )
    (net (code "37") (name "Net-(120-1)") (class "Default")
      (node (ref "120") (pin "P$1") (pinfunction "1_P$1") (pintype "passive"))
      (node (ref "C5") (pin "1") (pinfunction "1_1") (pintype "passive"))
      (node (ref "U$6") (pin "P$6") (pinfunction "VOUT_P$6") (pintype "bidirectional"))
    )
    (net (code "38") (name "Net-(ARMED-PadA)") (class "Default")
      (node (ref "ARMED") (pin "A") (pinfunction "A_A") (pintype "passive"))
      (node (ref "R20") (pin "1") (pinfunction "1_1") (pintype "passive"))
    )
    (net (code "39") (name "Net-(CHARGING-PadC)") (class "Default")
      (node (ref "CHARGING") (pin "C") (pinfunction "C_C") (pintype "passive"))
      (node (ref "R14") (pin "2") (pinfunction "2_2") (pintype "passive"))
    )
    (net (code "40") (name "Net-(DISCHARGING-PadC)") (class "Default")
      (node (ref "DISCHARGING") (pin "C") (pinfunction "C_C") (pintype "passive"))
      (node (ref "R17") (pin "2") (pinfunction "2_2") (pintype "passive"))
    )
    (net (code "41") (name "Net-(LIGHT1-PadC)") (class "Default")
      (node (ref "LIGHT1") (pin "C") (pinfunction "C_C") (pintype "passive"))
      (node (ref "R18") (pin "2") (pinfunction "2_2") (pintype "passive"))
    )
    (net (code "42") (name "Net-(LIGHT2-PadC)") (class "Default")
      (node (ref "LIGHT2") (pin "C") (pinfunction "C_C") (pintype "passive"))
      (node (ref "R19") (pin "2") (pinfunction "2_2") (pintype "passive"))
    )
    (net (code "43") (name "Net-(LIGHT3-PadC)") (class "Default")
      (node (ref "LIGHT3") (pin "C") (pinfunction "C_C") (pintype "passive"))
      (node (ref "R22") (pin "2") (pinfunction "2_2") (pintype "passive"))
    )
    (net (code "44") (name "Net-(LIGHT4-PadC)") (class "Default")
      (node (ref "LIGHT4") (pin "C") (pinfunction "C_C") (pintype "passive"))
      (node (ref "R23") (pin "2") (pinfunction "2_2") (pintype "passive"))
    )
    (net (code "45") (name "Net-(LIGHT5-PadC)") (class "Default")
      (node (ref "LIGHT5") (pin "C") (pinfunction "C_C") (pintype "passive"))
      (node (ref "R24") (pin "2") (pinfunction "2_2") (pintype "passive"))
    )
    (net (code "46") (name "Net-(LIGHT6-PadC)") (class "Default")
      (node (ref "LIGHT6") (pin "C") (pinfunction "C_C") (pintype "passive"))
      (node (ref "R25") (pin "2") (pinfunction "2_2") (pintype "passive"))
    )
    (net (code "47") (name "Net-(LIGHT7-PadC)") (class "Default")
      (node (ref "LIGHT7") (pin "C") (pinfunction "C_C") (pintype "passive"))
      (node (ref "R26") (pin "2") (pinfunction "2_2") (pintype "passive"))
    )
    (net (code "48") (name "Net-(LIGHT8-PadC)") (class "Default")
      (node (ref "LIGHT8") (pin "C") (pinfunction "C_C") (pintype "passive"))
      (node (ref "R28") (pin "2") (pinfunction "2_2") (pintype "passive"))
    )
    (net (code "49") (name "Net-(MC-BOOT0)") (class "Default")
      (node (ref "MC") (pin "60") (pinfunction "BOOT0_60") (pintype "bidirectional"))
      (node (ref "R30") (pin "1") (pinfunction "1_1") (pintype "passive"))
    )
    (net (code "50") (name "Net-(MC-PC14{slash}OSC32_IN)") (class "Default")
      (node (ref "C9") (pin "1") (pinfunction "1_1") (pintype "passive"))
      (node (ref "MC") (pin "3") (pinfunction "PC14/OSC32_IN_3") (pintype "bidirectional"))
      (node (ref "Y3") (pin "P$1") (pinfunction "1_P$1") (pintype "passive"))
    )
    (net (code "51") (name "Net-(MC-PC15{slash}OSC32_OUT)") (class "Default")
      (node (ref "C13") (pin "1") (pinfunction "1_1") (pintype "passive"))
      (node (ref "MC") (pin "4") (pinfunction "PC15/OSC32_OUT_4") (pintype "bidirectional"))
      (node (ref "Y3") (pin "P$2") (pinfunction "2_P$2") (pintype "passive"))
    )
    (net (code "52") (name "Net-(MC-PH0{slash}OSC_IN)") (class "Default")
      (node (ref "C3") (pin "1") (pinfunction "1_1") (pintype "passive"))
      (node (ref "MC") (pin "5") (pinfunction "PH0/OSC_IN_5") (pintype "bidirectional"))
      (node (ref "Y1") (pin "2") (pinfunction "2_2") (pintype "passive"))
    )
    (net (code "53") (name "Net-(MC-PH1{slash}OSC_OUT)") (class "Default")
      (node (ref "C2") (pin "1") (pinfunction "1_1") (pintype "passive"))
      (node (ref "MC") (pin "6") (pinfunction "PH1/OSC_OUT_6") (pintype "bidirectional"))
      (node (ref "Y1") (pin "1") (pinfunction "1_1") (pintype "passive"))
    )
    (net (code "54") (name "Net-(MC-VCAP_1)") (class "Default")
      (node (ref "C7") (pin "2") (pinfunction "2_2") (pintype "passive"))
      (node (ref "MC") (pin "31") (pinfunction "VCAP_1_31") (pintype "power_in"))
    )
    (net (code "55") (name "Net-(MC-VCAP_2)") (class "Default")
      (node (ref "C8") (pin "2") (pinfunction "2_2") (pintype "passive"))
      (node (ref "MC") (pin "47") (pinfunction "VCAP_2_47") (pintype "power_in"))
    )
    (net (code "56") (name "Net-(Q2-D)") (class "Default")
      (node (ref "Q2") (pin "3") (pinfunction "D_3") (pintype "bidirectional"))
      (node (ref "R44") (pin "1") (pinfunction "1_1") (pintype "passive"))
    )
    (net (code "57") (name "Net-(Q3-D)") (class "Default")
      (node (ref "Q3") (pin "3") (pinfunction "D_3") (pintype "bidirectional"))
      (node (ref "R12") (pin "1") (pinfunction "1_1") (pintype "passive"))
    )
    (net (code "58") (name "Net-(Q6-G)") (class "Default")
      (node (ref "Q6") (pin "1") (pinfunction "G_1") (pintype "passive"))
      (node (ref "R12") (pin "2") (pinfunction "2_2") (pintype "passive"))
      (node (ref "R9") (pin "1") (pinfunction "1_1") (pintype "passive"))
    )
    (net (code "59") (name "Net-(Q18-G)") (class "Default")
      (node (ref "Q18") (pin "1") (pinfunction "G_1") (pintype "passive"))
      (node (ref "R43") (pin "1") (pinfunction "1_1") (pintype "passive"))
      (node (ref "R44") (pin "2") (pinfunction "2_2") (pintype "passive"))
    )
    (net (code "60") (name "Net-(R1-Pad1)") (class "Default")
      (node (ref "R1") (pin "1") (pinfunction "1_1") (pintype "passive"))
      (node (ref "USB_ID/USB_DP/USB_DN") (pin "D+") (pinfunction "D+_D+") (pintype "bidirectional"))
    )
    (net (code "61") (name "Net-(R11-Pad1)") (class "Default")
      (node (ref "R11") (pin "1") (pinfunction "1_1") (pintype "passive"))
      (node (ref "USB_ID/USB_DP/USB_DN") (pin "ID") (pinfunction "ID_ID") (pintype "bidirectional"))
    )
    (net (code "62") (name "Net-(R13-Pad1)") (class "Default")
      (node (ref "R13") (pin "1") (pinfunction "1_1") (pintype "passive"))
      (node (ref "USB_ID/USB_DP/USB_DN") (pin "D-") (pinfunction "D-_D-") (pintype "bidirectional"))
    )
    (net (code "63") (name "Net-(U1-CP1)") (class "Default")
      (node (ref "C18") (pin "2") (pinfunction "2_2") (pintype "passive"))
      (node (ref "U1") (pin "11") (pinfunction "CP1_11") (pintype "passive"))
    )
    (net (code "64") (name "Net-(U1-CP2)") (class "Default")
      (node (ref "C18") (pin "1") (pinfunction "1_1") (pintype "passive"))
      (node (ref "U1") (pin "12") (pinfunction "CP2_12") (pintype "passive"))
    )
    (net (code "65") (name "Net-(U1-SENSE)") (class "Default")
      (node (ref "R4") (pin "2") (pinfunction "2_2") (pintype "passive"))
      (node (ref "U1") (pin "8") (pinfunction "SENSE_8") (pintype "output"))
    )
    (net (code "66") (name "Net-(U1-VBB)") (class "Default")
      (node (ref "C16") (pin "1") (pinfunction "1_1") (pintype "passive"))
      (node (ref "C17") (pin "1") (pinfunction "1_1") (pintype "passive"))
      (node (ref "C19") (pin "1") (pinfunction "1_1") (pintype "passive"))
      (node (ref "U1") (pin "9") (pinfunction "VBB_9") (pintype "power_in"))
    )
    (net (code "67") (name "Net-(U1-VCP)") (class "Default")
      (node (ref "C17") (pin "2") (pinfunction "2_2") (pintype "passive"))
      (node (ref "U1") (pin "14") (pinfunction "VCP_14") (pintype "output"))
    )
    (net (code "68") (name "PWM_CLAW") (class "Default")
      (node (ref "CLAW_CONTROL") (pin "4") (pinfunction "4_4") (pintype "passive"))
      (node (ref "MC") (pin "14") (pinfunction "PA0/WKUP_14") (pintype "bidirectional"))
    )
    (net (code "69") (name "PWM_DRIVER1") (class "Default")
      (node (ref "MC") (pin "15") (pinfunction "PA1/USART2_RTS_15") (pintype "bidirectional"))
      (node (ref "U1") (pin "3") (pinfunction "IN1_3") (pintype "input"))
    )
    (net (code "70") (name "PWM_DRIVER2") (class "Default")
      (node (ref "MC") (pin "16") (pinfunction "PA2/USART2_TX_16") (pintype "bidirectional"))
      (node (ref "U1") (pin "16") (pinfunction "IN2_16") (pintype "input"))
    )
    (net (code "71") (name "PWM_OUT1") (class "Default")
      (node (ref "CLAW_CONTROL") (pin "5") (pinfunction "5_5") (pintype "passive"))
      (node (ref "U1") (pin "7") (pinfunction "OUT1_7") (pintype "output"))
    )
    (net (code "72") (name "PWM_OUT2") (class "Default")
      (node (ref "CLAW_CONTROL") (pin "6") (pinfunction "6_6") (pintype "passive"))
      (node (ref "U1") (pin "10") (pinfunction "OUT2_10") (pintype "output"))
    )
    (net (code "73") (name "RESET") (class "Default")
      (node (ref "JTAG_HEADER") (pin "15") (pinfunction "15_15") (pintype "passive"))
      (node (ref "MC") (pin "7") (pinfunction "NRST_7") (pintype "bidirectional"))
      (node (ref "R27") (pin "1") (pinfunction "1_1") (pintype "passive"))
      (node (ref "RESET_SWITCH") (pin "3") (pinfunction "2_3") (pintype "passive"))
    )
    (net (code "74") (name "SCL") (class "Default")
      (node (ref "MC") (pin "58") (pinfunction "PB6_58") (pintype "bidirectional"))
      (node (ref "U$1") (pin "31") (pinfunction "BOARD_SCL_31") (pintype "bidirectional"))
    )
    (net (code "75") (name "SDA") (class "Default")
      (node (ref "MC") (pin "59") (pinfunction "PB7_59") (pintype "bidirectional"))
      (node (ref "U$1") (pin "32") (pinfunction "BOARD_SDA_32") (pintype "bidirectional"))
    )
    (net (code "76") (name "SMBA") (class "Default")
      (node (ref "MC") (pin "57") (pinfunction "PB5_57") (pintype "bidirectional"))
    )
    (net (code "77") (name "SWD_CLK") (class "Default")
      (node (ref "JTAG_HEADER") (pin "9") (pinfunction "9_9") (pintype "passive"))
      (node (ref "MC") (pin "49") (pinfunction "PA14/JTCK-SWCLK_49") (pintype "bidirectional"))
    )
    (net (code "78") (name "SWD_IO") (class "Default")
      (node (ref "JTAG_HEADER") (pin "7") (pinfunction "7_7") (pintype "passive"))
      (node (ref "MC") (pin "46") (pinfunction "PA13/JMS-SWDIO_46") (pintype "bidirectional"))
    )
    (net (code "79") (name "TORPEDO1") (class "Default")
      (node (ref "Q18") (pin "3") (pinfunction "D_3") (pintype "passive"))
      (node (ref "TORPEDO_CONNECTOR") (pin "1") (pinfunction "1_1") (pintype "passive"))
    )
    (net (code "80") (name "TORPEDO1_GATE") (class "Default")
      (node (ref "MC") (pin "37") (pinfunction "PC6_37") (pintype "bidirectional"))
      (node (ref "Q2") (pin "1") (pinfunction "G_1") (pintype "bidirectional"))
    )
    (net (code "81") (name "TORPEDO2") (class "Default")
      (node (ref "Q6") (pin "3") (pinfunction "D_3") (pintype "passive"))
      (node (ref "TORPEDO_CONNECTOR") (pin "2") (pinfunction "2_2") (pintype "passive"))
    )
    (net (code "82") (name "TORPEDO2_GATE") (class "Default")
      (node (ref "MC") (pin "38") (pinfunction "PC7_38") (pintype "bidirectional"))
      (node (ref "Q3") (pin "1") (pinfunction "G_1") (pintype "bidirectional"))
    )
    (net (code "83") (name "USB_DN") (class "Default")
      (node (ref "MC") (pin "44") (pinfunction "PA11_44") (pintype "bidirectional"))
      (node (ref "R13") (pin "2") (pinfunction "2_2") (pintype "passive"))
    )
    (net (code "84") (name "USB_DP") (class "Default")
      (node (ref "MC") (pin "45") (pinfunction "PA12_45") (pintype "bidirectional"))
      (node (ref "R1") (pin "2") (pinfunction "2_2") (pintype "passive"))
    )
    (net (code "85") (name "USB_ID") (class "Default")
      (node (ref "R11") (pin "2") (pinfunction "2_2") (pintype "passive"))
      (node (ref "R2") (pin "1") (pinfunction "1_1") (pintype "passive"))
    )
    (net (code "86") (name "V+") (class "Default")
      (node (ref "POWER_INPUT") (pin "4") (pinfunction "4_4") (pintype "passive"))
      (node (ref "U$6") (pin "P$2") (pinfunction "VIN_P$2") (pintype "bidirectional"))
    )
    (net (code "87") (name "VBAT") (class "Default")
      (node (ref "MC") (pin "1") (pinfunction "VBAT_1") (pintype "power_in"))
    )
    (net (code "88") (name "VBUS") (class "Default")
      (node (ref "C14") (pin "1") (pinfunction "1_1") (pintype "passive"))
      (node (ref "USB_ID/USB_DP/USB_DN") (pin "VBUS") (pinfunction "VBUS_VBUS") (pintype "power_in"))
      (node (ref "VR1") (pin "3") (pinfunction "VIN_3") (pintype "input"))
    )
    (net (code "89") (name "unconnected-(JTAG_HEADER-Pad3)") (class "Default")
      (node (ref "JTAG_HEADER") (pin "3") (pinfunction "3_3") (pintype "passive"))
    )
    (net (code "90") (name "unconnected-(JTAG_HEADER-Pad5)") (class "Default")
      (node (ref "JTAG_HEADER") (pin "5") (pinfunction "5_5") (pintype "passive"))
    )
    (net (code "91") (name "unconnected-(JTAG_HEADER-Pad11)") (class "Default")
      (node (ref "JTAG_HEADER") (pin "11") (pinfunction "11_11") (pintype "passive"))
    )
    (net (code "92") (name "unconnected-(JTAG_HEADER-Pad13)") (class "Default")
      (node (ref "JTAG_HEADER") (pin "13") (pinfunction "13_13") (pintype "passive"))
    )
    (net (code "93") (name "unconnected-(JTAG_HEADER-Pad17)") (class "Default")
      (node (ref "JTAG_HEADER") (pin "17") (pinfunction "17_17") (pintype "passive"))
    )
    (net (code "94") (name "unconnected-(JTAG_HEADER-Pad19)") (class "Default")
      (node (ref "JTAG_HEADER") (pin "19") (pinfunction "19_19") (pintype "passive"))
    )
    (net (code "95") (name "unconnected-(MC-PA3{slash}USART2_RX-Pad17)") (class "Default")
      (node (ref "MC") (pin "17") (pinfunction "PA3/USART2_RX_17") (pintype "bidirectional"))
    )
    (net (code "96") (name "unconnected-(MC-PA8-Pad41)") (class "Default")
      (node (ref "MC") (pin "41") (pinfunction "PA8_41") (pintype "bidirectional"))
    )
    (net (code "97") (name "unconnected-(MC-PA9-Pad42)") (class "Default")
      (node (ref "MC") (pin "42") (pinfunction "PA9_42") (pintype "bidirectional"))
    )
    (net (code "98") (name "unconnected-(MC-PA10-Pad43)") (class "Default")
      (node (ref "MC") (pin "43") (pinfunction "PA10_43") (pintype "bidirectional"))
    )
    (net (code "99") (name "unconnected-(MC-PA15-Pad50)") (class "Default")
      (node (ref "MC") (pin "50") (pinfunction "PA15_50") (pintype "bidirectional"))
    )
    (net (code "100") (name "unconnected-(MC-PB2{slash}BOOT1-Pad28)") (class "Default")
      (node (ref "MC") (pin "28") (pinfunction "PB2/BOOT1_28") (pintype "bidirectional"))
    )
    (net (code "101") (name "unconnected-(MC-PC0-Pad8)") (class "Default")
      (node (ref "MC") (pin "8") (pinfunction "PC0_8") (pintype "bidirectional"))
    )
    (net (code "102") (name "unconnected-(MC-PC1-Pad9)") (class "Default")
      (node (ref "MC") (pin "9") (pinfunction "PC1_9") (pintype "bidirectional"))
    )
    (net (code "103") (name "unconnected-(MC-PC2{slash}SPI2_MISO-Pad10)") (class "Default")
      (node (ref "MC") (pin "10") (pinfunction "PC2/SPI2_MISO_10") (pintype "bidirectional"))
    )
    (net (code "104") (name "unconnected-(MC-PC3{slash}SPI2_MOSI-Pad11)") (class "Default")
      (node (ref "MC") (pin "11") (pinfunction "PC3/SPI2_MOSI_11") (pintype "bidirectional"))
    )
    (net (code "105") (name "unconnected-(MC-PC9-Pad40)") (class "Default")
      (node (ref "MC") (pin "40") (pinfunction "PC9_40") (pintype "bidirectional"))
    )
    (net (code "106") (name "unconnected-(MC-PC13{slash}RTC_OUT-Pad2)") (class "Default")
      (node (ref "MC") (pin "2") (pinfunction "PC13/RTC_OUT_2") (pintype "bidirectional"))
    )
    (net (code "107") (name "unconnected-(U$1-3.3V_ON{slash}OFF-Pad14)") (class "Default")
      (node (ref "U$1") (pin "14") (pinfunction "3.3V_ON/OFF_14") (pintype "bidirectional"))
    )
    (net (code "108") (name "unconnected-(U$1-5V_ON_OFF-Pad15)") (class "Default")
      (node (ref "U$1") (pin "15") (pinfunction "5V_ON_OFF_15") (pintype "bidirectional"))
    )
    (net (code "109") (name "unconnected-(U$1-12V_ON{slash}OFF-Pad16)") (class "Default")
      (node (ref "U$1") (pin "16") (pinfunction "12V_ON/OFF_16") (pintype "bidirectional"))
    )
    (net (code "110") (name "unconnected-(U$1-ACOUSTIC_ON{slash}OFF-Pad17)") (class "Default")
      (node (ref "U$1") (pin "17") (pinfunction "ACOUSTIC_ON/OFF_17") (pintype "bidirectional"))
    )
    (net (code "111") (name "unconnected-(U$1-JETSON_ON{slash}OFF-Pad18)") (class "Default")
      (node (ref "U$1") (pin "18") (pinfunction "JETSON_ON/OFF_18") (pintype "bidirectional"))
    )
    (net (code "112") (name "unconnected-(U$1-KILL_SWITCH-Pad37)") (class "Default")
      (node (ref "U$1") (pin "37") (pinfunction "KILL_SWITCH_37") (pintype "output"))
    )
    (net (code "113") (name "unconnected-(U$1-MOBO_ON{slash}OFF-Pad19)") (class "Default")
      (node (ref "U$1") (pin "19") (pinfunction "MOBO_ON/OFF_19") (pintype "bidirectional"))
    )
    (net (code "114") (name "unconnected-(U$1-PWM_1-Pad20)") (class "Default")
      (node (ref "U$1") (pin "20") (pinfunction "PWM_1_20") (pintype "bidirectional"))
    )
    (net (code "115") (name "unconnected-(U$1-PWM_2-Pad21)") (class "Default")
      (node (ref "U$1") (pin "21") (pinfunction "PWM_2_21") (pintype "bidirectional"))
    )
    (net (code "116") (name "unconnected-(U$1-PWM_3-Pad22)") (class "Default")
      (node (ref "U$1") (pin "22") (pinfunction "PWM_3_22") (pintype "bidirectional"))
    )
    (net (code "117") (name "unconnected-(U$1-PWM_4-Pad23)") (class "Default")
      (node (ref "U$1") (pin "23") (pinfunction "PWM_4_23") (pintype "bidirectional"))
    )
    (net (code "118") (name "unconnected-(U$1-PWM_5-Pad24)") (class "Default")
      (node (ref "U$1") (pin "24") (pinfunction "PWM_5_24") (pintype "bidirectional"))
    )
    (net (code "119") (name "unconnected-(U$1-PWM_6-Pad25)") (class "Default")
      (node (ref "U$1") (pin "25") (pinfunction "PWM_6_25") (pintype "bidirectional"))
    )
    (net (code "120") (name "unconnected-(U$1-PWM_7-Pad26)") (class "Default")
      (node (ref "U$1") (pin "26") (pinfunction "PWM_7_26") (pintype "bidirectional"))
    )
    (net (code "121") (name "unconnected-(U$1-PWM_8-Pad27)") (class "Default")
      (node (ref "U$1") (pin "27") (pinfunction "PWM_8_27") (pintype "bidirectional"))
    )
    (net (code "122") (name "unconnected-(U$1-SENSOR_SCL-Pad29)") (class "Default")
      (node (ref "U$1") (pin "29") (pinfunction "SENSOR_SCL_29") (pintype "bidirectional"))
    )
    (net (code "123") (name "unconnected-(U$1-SENSOR_SDA-Pad30)") (class "Default")
      (node (ref "U$1") (pin "30") (pinfunction "SENSOR_SDA_30") (pintype "bidirectional"))
    )
    (net (code "124") (name "unconnected-(U$1-SPARE1-Pad7)") (class "Default")
      (node (ref "U$1") (pin "7") (pinfunction "SPARE1_7") (pintype "bidirectional"))
    )
    (net (code "125") (name "unconnected-(U$1-SPARE3-Pad33)") (class "Default")
      (node (ref "U$1") (pin "33") (pinfunction "SPARE3_33") (pintype "bidirectional"))
    )
    (net (code "126") (name "unconnected-(U$1-SPARE4-Pad34)") (class "Default")
      (node (ref "U$1") (pin "34") (pinfunction "SPARE4_34") (pintype "bidirectional"))
    )
    (net (code "127") (name "unconnected-(U$1-SPARE8-Pad50)") (class "Default")
      (node (ref "U$1") (pin "50") (pinfunction "SPARE8_50") (pintype "bidirectional"))
    )
    (net (code "128") (name "unconnected-(U$1-SWITCH_1-Pad38)") (class "Default")
      (node (ref "U$1") (pin "38") (pinfunction "SWITCH_1_38") (pintype "output"))
    )
    (net (code "129") (name "unconnected-(U$1-SWITCH_2-Pad39)") (class "Default")
      (node (ref "U$1") (pin "39") (pinfunction "SWITCH_2_39") (pintype "output"))
    )
    (net (code "130") (name "unconnected-(U$1-SWITCH_3-Pad40)") (class "Default")
      (node (ref "U$1") (pin "40") (pinfunction "SWITCH_3_40") (pintype "output"))
    )
    (net (code "131") (name "unconnected-(U$1-SWITCH_4-Pad41)") (class "Default")
      (node (ref "U$1") (pin "41") (pinfunction "SWITCH_4_41") (pintype "output"))
    )
    (net (code "132") (name "unconnected-(U$1-SWITCH_5-Pad42)") (class "Default")
      (node (ref "U$1") (pin "42") (pinfunction "SWITCH_5_42") (pintype "output"))
    )
    (net (code "133") (name "unconnected-(U1-NFAULT-Pad1)") (class "Default")
      (node (ref "U1") (pin "1") (pinfunction "NFAULT_1") (pintype "output"))
    )
    (net (code "134") (name "unconnected-(U1-VPROPI-Pad15)") (class "Default")
      (node (ref "U1") (pin "15") (pinfunction "VPROPI_15") (pintype "output"))
    )
    (net (code "135") (name "unconnected-(VR1-VOUT_4-Pad4)") (class "Default")
      (node (ref "VR1") (pin "4") (pinfunction "VOUT_4_4") (pintype "output"))
    )
  )
)
